# dds_ad9958.net
KiCad netlist of a schematic drawn in EAGLE
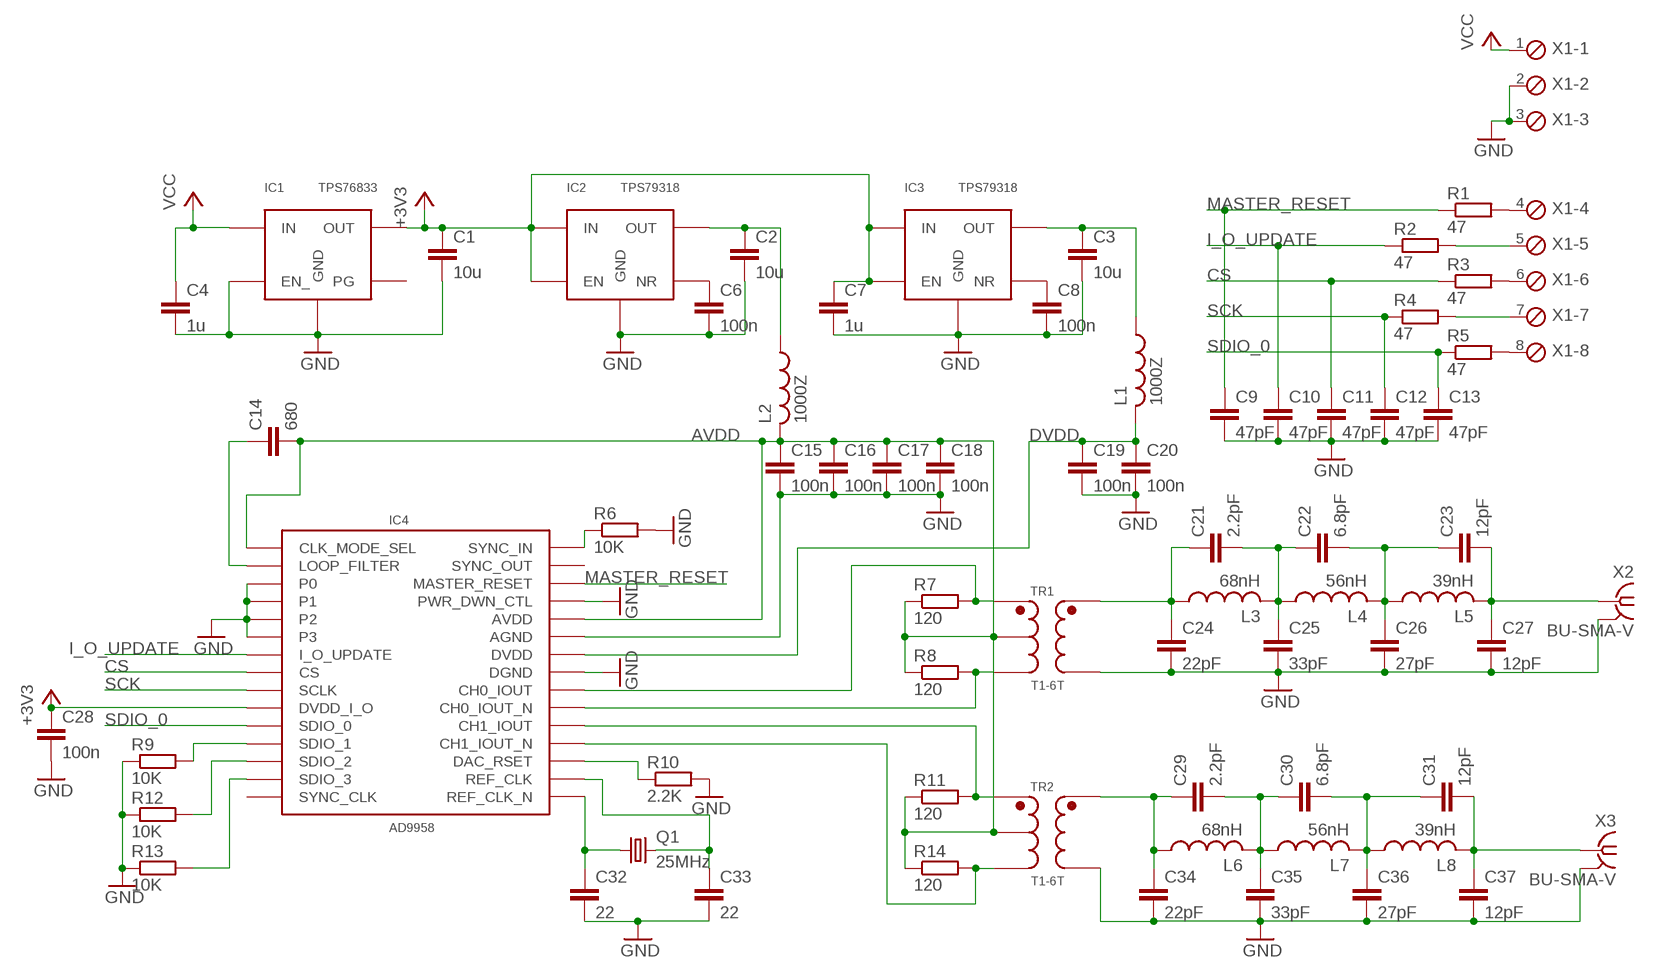
[diagram p0: schematic, sheet 1]

(export (version "E")
  (design (tool "Eeschema 10.0.6"))
  (components
    (comp (ref "C1")
      (value "10u")
      (footprint "eagle-import:C0805")
      (libsource (lib "eagle-import") (part "C-EUC0805"))
    )
    (comp (ref "C2")
      (value "10u")
      (footprint "eagle-import:C0805")
      (libsource (lib "eagle-import") (part "C-EUC0805"))
    )
    (comp (ref "C3")
      (value "10u")
      (footprint "eagle-import:C0805")
      (libsource (lib "eagle-import") (part "C-EUC0805"))
    )
    (comp (ref "C4")
      (value "1u")
      (footprint "eagle-import:C0603")
      (libsource (lib "eagle-import") (part "C-EUC0603"))
    )
    (comp (ref "C6")
      (value "100n")
      (footprint "eagle-import:C0603")
      (libsource (lib "eagle-import") (part "C-EUC0603"))
    )
    (comp (ref "C7")
      (value "1u")
      (footprint "eagle-import:C0603")
      (libsource (lib "eagle-import") (part "C-EUC0603"))
    )
    (comp (ref "C8")
      (value "100n")
      (footprint "eagle-import:C0603")
      (libsource (lib "eagle-import") (part "C-EUC0603"))
    )
    (comp (ref "C9")
      (value "47pF")
      (footprint "eagle-import:C0805")
      (libsource (lib "eagle-import") (part "C-EUC0805"))
    )
    (comp (ref "C10")
      (value "47pF")
      (footprint "eagle-import:C0805")
      (libsource (lib "eagle-import") (part "C-EUC0805"))
    )
    (comp (ref "C11")
      (value "47pF")
      (footprint "eagle-import:C0805")
      (libsource (lib "eagle-import") (part "C-EUC0805"))
    )
    (comp (ref "C12")
      (value "47pF")
      (footprint "eagle-import:C0805")
      (libsource (lib "eagle-import") (part "C-EUC0805"))
    )
    (comp (ref "C13")
      (value "47pF")
      (footprint "eagle-import:C0805")
      (libsource (lib "eagle-import") (part "C-EUC0805"))
    )
    (comp (ref "C14")
      (value "680")
      (footprint "eagle-import:C0805")
      (libsource (lib "eagle-import") (part "C-EUC0805"))
    )
    (comp (ref "C15")
      (value "100n")
      (footprint "eagle-import:C0603")
      (libsource (lib "eagle-import") (part "C-EUC0603"))
    )
    (comp (ref "C16")
      (value "100n")
      (footprint "eagle-import:C0603")
      (libsource (lib "eagle-import") (part "C-EUC0603"))
    )
    (comp (ref "C17")
      (value "100n")
      (footprint "eagle-import:C0603")
      (libsource (lib "eagle-import") (part "C-EUC0603"))
    )
    (comp (ref "C18")
      (value "100n")
      (footprint "eagle-import:C0603")
      (libsource (lib "eagle-import") (part "C-EUC0603"))
    )
    (comp (ref "C19")
      (value "100n")
      (footprint "eagle-import:C0603")
      (libsource (lib "eagle-import") (part "C-EUC0603"))
    )
    (comp (ref "C20")
      (value "100n")
      (footprint "eagle-import:C0603")
      (libsource (lib "eagle-import") (part "C-EUC0603"))
    )
    (comp (ref "C21")
      (value "2.2pF")
      (footprint "eagle-import:C0805")
      (libsource (lib "eagle-import") (part "C-EUC0805"))
    )
    (comp (ref "C22")
      (value "6.8pF")
      (footprint "eagle-import:C0805")
      (libsource (lib "eagle-import") (part "C-EUC0805"))
    )
    (comp (ref "C23")
      (value "12pF")
      (footprint "eagle-import:C0805")
      (libsource (lib "eagle-import") (part "C-EUC0805"))
    )
    (comp (ref "C24")
      (value "22pF")
      (footprint "eagle-import:C0805")
      (libsource (lib "eagle-import") (part "C-EUC0805"))
    )
    (comp (ref "C25")
      (value "33pF")
      (footprint "eagle-import:C0805")
      (libsource (lib "eagle-import") (part "C-EUC0805"))
    )
    (comp (ref "C26")
      (value "27pF")
      (footprint "eagle-import:C0805")
      (libsource (lib "eagle-import") (part "C-EUC0805"))
    )
    (comp (ref "C27")
      (value "12pF")
      (footprint "eagle-import:C0805")
      (libsource (lib "eagle-import") (part "C-EUC0805"))
    )
    (comp (ref "C28")
      (value "100n")
      (footprint "eagle-import:C0603")
      (libsource (lib "eagle-import") (part "C-EUC0603"))
    )
    (comp (ref "C29")
      (value "2.2pF")
      (footprint "eagle-import:C0805")
      (libsource (lib "eagle-import") (part "C-EUC0805"))
    )
    (comp (ref "C30")
      (value "6.8pF")
      (footprint "eagle-import:C0805")
      (libsource (lib "eagle-import") (part "C-EUC0805"))
    )
    (comp (ref "C31")
      (value "12pF")
      (footprint "eagle-import:C0805")
      (libsource (lib "eagle-import") (part "C-EUC0805"))
    )
    (comp (ref "C32")
      (value "22")
      (footprint "eagle-import:C0603")
      (libsource (lib "eagle-import") (part "C-EUC0603"))
    )
    (comp (ref "C33")
      (value "22")
      (footprint "eagle-import:C0603")
      (libsource (lib "eagle-import") (part "C-EUC0603"))
    )
    (comp (ref "C34")
      (value "22pF")
      (footprint "eagle-import:C0805")
      (libsource (lib "eagle-import") (part "C-EUC0805"))
    )
    (comp (ref "C35")
      (value "33pF")
      (footprint "eagle-import:C0805")
      (libsource (lib "eagle-import") (part "C-EUC0805"))
    )
    (comp (ref "C36")
      (value "27pF")
      (footprint "eagle-import:C0805")
      (libsource (lib "eagle-import") (part "C-EUC0805"))
    )
    (comp (ref "C37")
      (value "12pF")
      (footprint "eagle-import:C0805")
      (libsource (lib "eagle-import") (part "C-EUC0805"))
    )
    (comp (ref "IC1")
      (value "TPS76833")
      (footprint "eagle-import:SO8")
      (libsource (lib "eagle-import") (part "TPS768XX"))
    )
    (comp (ref "IC2")
      (value "TPS79318")
      (footprint "eagle-import:SOT23-5")
      (libsource (lib "eagle-import") (part "TPS793XX_FIXED"))
    )
    (comp (ref "IC3")
      (value "TPS79318")
      (footprint "eagle-import:SOT23-5")
      (libsource (lib "eagle-import") (part "TPS793XX_FIXED"))
    )
    (comp (ref "IC4")
      (value "AD9958")
      (footprint "eagle-import:CP-56-1")
      (libsource (lib "eagle-import") (part "AD9958"))
    )
    (comp (ref "L1")
      (value "1000Z")
      (footprint "eagle-import:C0805")
      (libsource (lib "eagle-import") (part "L-USL0805"))
    )
    (comp (ref "L2")
      (value "1000Z")
      (footprint "eagle-import:C0805")
      (libsource (lib "eagle-import") (part "L-USL0805"))
    )
    (comp (ref "L3")
      (value "68nH")
      (footprint "eagle-import:C0805")
      (libsource (lib "eagle-import") (part "L-USL0805"))
    )
    (comp (ref "L4")
      (value "56nH")
      (footprint "eagle-import:C0805")
      (libsource (lib "eagle-import") (part "L-USL0805"))
    )
    (comp (ref "L5")
      (value "39nH")
      (footprint "eagle-import:C0805")
      (libsource (lib "eagle-import") (part "L-USL0805"))
    )
    (comp (ref "L6")
      (value "68nH")
      (footprint "eagle-import:C0805")
      (libsource (lib "eagle-import") (part "L-USL0805"))
    )
    (comp (ref "L7")
      (value "56nH")
      (footprint "eagle-import:C0805")
      (libsource (lib "eagle-import") (part "L-USL0805"))
    )
    (comp (ref "L8")
      (value "39nH")
      (footprint "eagle-import:C0805")
      (libsource (lib "eagle-import") (part "L-USL0805"))
    )
    (comp (ref "Q1")
      (value "25MHz")
      (footprint "eagle-import:HC49_S")
      (libsource (lib "eagle-import") (part "CRYSTALHC49S"))
    )
    (comp (ref "R1")
      (value "47")
      (footprint "eagle-import:R0603")
      (libsource (lib "eagle-import") (part "R-EU_R0603"))
    )
    (comp (ref "R2")
      (value "47")
      (footprint "eagle-import:R0603")
      (libsource (lib "eagle-import") (part "R-EU_R0603"))
    )
    (comp (ref "R3")
      (value "47")
      (footprint "eagle-import:R0603")
      (libsource (lib "eagle-import") (part "R-EU_R0603"))
    )
    (comp (ref "R4")
      (value "47")
      (footprint "eagle-import:R0603")
      (libsource (lib "eagle-import") (part "R-EU_R0603"))
    )
    (comp (ref "R5")
      (value "47")
      (footprint "eagle-import:R0603")
      (libsource (lib "eagle-import") (part "R-EU_R0603"))
    )
    (comp (ref "R6")
      (value "10K")
      (footprint "eagle-import:R0603")
      (libsource (lib "eagle-import") (part "R-EU_R0603"))
    )
    (comp (ref "R7")
      (value "120")
      (footprint "eagle-import:R0603")
      (libsource (lib "eagle-import") (part "R-EU_R0603"))
    )
    (comp (ref "R8")
      (value "120")
      (footprint "eagle-import:R0603")
      (libsource (lib "eagle-import") (part "R-EU_R0603"))
    )
    (comp (ref "R9")
      (value "10K")
      (footprint "eagle-import:R0603")
      (libsource (lib "eagle-import") (part "R-EU_R0603"))
    )
    (comp (ref "R10")
      (value "2.2K")
      (footprint "eagle-import:R0603")
      (libsource (lib "eagle-import") (part "R-EU_R0603"))
    )
    (comp (ref "R11")
      (value "120")
      (footprint "eagle-import:R0603")
      (libsource (lib "eagle-import") (part "R-EU_R0603"))
    )
    (comp (ref "R12")
      (value "10K")
      (footprint "eagle-import:R0603")
      (libsource (lib "eagle-import") (part "R-EU_R0603"))
    )
    (comp (ref "R13")
      (value "10K")
      (footprint "eagle-import:R0603")
      (libsource (lib "eagle-import") (part "R-EU_R0603"))
    )
    (comp (ref "R14")
      (value "120")
      (footprint "eagle-import:R0603")
      (libsource (lib "eagle-import") (part "R-EU_R0603"))
    )
    (comp (ref "TR1")
      (value "T1-6T")
      (footprint "eagle-import:KK81")
      (libsource (lib "eagle-import") (part "T1-6T"))
    )
    (comp (ref "TR2")
      (value "T1-6T")
      (footprint "eagle-import:KK81")
      (libsource (lib "eagle-import") (part "T1-6T"))
    )
    (comp (ref "X1")
      (value "MPT8")
      (footprint "eagle-import:8POL254")
      (libsource (lib "eagle-import") (part "MPT8"))
    )
    (comp (ref "X2")
      (value "BU-SMA-V")
      (footprint "eagle-import:BU-SMA-V")
      (libsource (lib "eagle-import") (part "BU-SMA-V"))
    )
    (comp (ref "X3")
      (value "BU-SMA-V")
      (footprint "eagle-import:BU-SMA-V")
      (libsource (lib "eagle-import") (part "BU-SMA-V"))
    )
  )
  (nets
    (net (code "1") (name "+3V3") (class "Default")
      (node (ref "C1") (pin "1") (pinfunction "1_1") (pintype "passive"))
      (node (ref "C28") (pin "1") (pinfunction "1_1") (pintype "passive"))
      (node (ref "C7") (pin "1") (pinfunction "1_1") (pintype "passive"))
      (node (ref "IC1") (pin "5") (pinfunction "OUT_5") (pintype "bidirectional"))
      (node (ref "IC1") (pin "6") (pinfunction "OUT_6") (pintype "bidirectional"))
      (node (ref "IC2") (pin "1") (pinfunction "IN_1") (pintype "bidirectional"))
      (node (ref "IC2") (pin "3") (pinfunction "EN_3") (pintype "bidirectional"))
      (node (ref "IC3") (pin "1") (pinfunction "IN_1") (pintype "bidirectional"))
      (node (ref "IC3") (pin "3") (pinfunction "EN_3") (pintype "bidirectional"))
      (node (ref "IC4") (pin "P$49") (pinfunction "DVDD_I_O_P$49") (pintype "bidirectional"))
    )
    (net (code "2") (name "/AVDD") (class "Default")
      (node (ref "C14") (pin "2") (pinfunction "2_2") (pintype "passive"))
      (node (ref "C15") (pin "1") (pinfunction "1_1") (pintype "passive"))
      (node (ref "C16") (pin "1") (pinfunction "1_1") (pintype "passive"))
      (node (ref "C17") (pin "1") (pinfunction "1_1") (pintype "passive"))
      (node (ref "C18") (pin "1") (pinfunction "1_1") (pintype "passive"))
      (node (ref "IC4") (pin "P$11") (pinfunction "AVDD_P$11") (pintype "bidirectional"))
      (node (ref "IC4") (pin "P$15") (pinfunction "AVDD_P$15") (pintype "bidirectional"))
      (node (ref "IC4") (pin "P$19") (pinfunction "AVDD_P$19") (pintype "bidirectional"))
      (node (ref "IC4") (pin "P$21") (pinfunction "AVDD_P$21") (pintype "bidirectional"))
      (node (ref "IC4") (pin "P$24") (pinfunction "CLK_MODE_SEL_P$24") (pintype "bidirectional"))
      (node (ref "IC4") (pin "P$26") (pinfunction "AVDD_P$26") (pintype "bidirectional"))
      (node (ref "IC4") (pin "P$29") (pinfunction "AVDD_P$29") (pintype "bidirectional"))
      (node (ref "IC4") (pin "P$30") (pinfunction "AVDD_P$30") (pintype "bidirectional"))
      (node (ref "IC4") (pin "P$31") (pinfunction "AVDD_P$31") (pintype "bidirectional"))
      (node (ref "IC4") (pin "P$33") (pinfunction "AVDD_P$33") (pintype "bidirectional"))
      (node (ref "IC4") (pin "P$35") (pinfunction "AVDD_P$35") (pintype "bidirectional"))
      (node (ref "IC4") (pin "P$36") (pinfunction "AVDD_P$36") (pintype "bidirectional"))
      (node (ref "IC4") (pin "P$37") (pinfunction "AVDD_P$37") (pintype "bidirectional"))
      (node (ref "IC4") (pin "P$39") (pinfunction "AVDD_P$39") (pintype "bidirectional"))
      (node (ref "IC4") (pin "P$5") (pinfunction "AVDD_P$5") (pintype "bidirectional"))
      (node (ref "IC4") (pin "P$7") (pinfunction "AVDD_P$7") (pintype "bidirectional"))
      (node (ref "L2") (pin "2") (pinfunction "2_2") (pintype "passive"))
      (node (ref "R11") (pin "1") (pinfunction "1_1") (pintype "passive"))
      (node (ref "R14") (pin "1") (pinfunction "1_1") (pintype "passive"))
      (node (ref "R7") (pin "1") (pinfunction "1_1") (pintype "passive"))
      (node (ref "R8") (pin "1") (pinfunction "1_1") (pintype "passive"))
      (node (ref "TR1") (pin "P$2") (pinfunction "SEC_CT_P$2") (pintype "bidirectional"))
      (node (ref "TR2") (pin "P$2") (pinfunction "SEC_CT_P$2") (pintype "bidirectional"))
    )
    (net (code "3") (name "/CS") (class "Default")
      (node (ref "C11") (pin "1") (pinfunction "1_1") (pintype "passive"))
      (node (ref "IC4") (pin "P$47") (pinfunction "CS_P$47") (pintype "bidirectional"))
      (node (ref "R3") (pin "1") (pinfunction "1_1") (pintype "passive"))
    )
    (net (code "4") (name "/DVDD") (class "Default")
      (node (ref "C19") (pin "1") (pinfunction "1_1") (pintype "passive"))
      (node (ref "C20") (pin "1") (pinfunction "1_1") (pintype "passive"))
      (node (ref "IC4") (pin "P$45") (pinfunction "DVDD_P$45") (pintype "bidirectional"))
      (node (ref "IC4") (pin "P$55") (pinfunction "DVDD_P$55") (pintype "bidirectional"))
      (node (ref "L1") (pin "2") (pinfunction "2_2") (pintype "passive"))
    )
    (net (code "5") (name "/I_O_UPDATE") (class "Default")
      (node (ref "C10") (pin "1") (pinfunction "1_1") (pintype "passive"))
      (node (ref "IC4") (pin "P$46") (pinfunction "I_O_UPDATE_P$46") (pintype "bidirectional"))
      (node (ref "R2") (pin "1") (pinfunction "1_1") (pintype "passive"))
    )
    (net (code "6") (name "/MASTER_RESET") (class "Default")
      (node (ref "C9") (pin "1") (pinfunction "1_1") (pintype "passive"))
      (node (ref "IC4") (pin "P$3") (pinfunction "MASTER_RESET_P$3") (pintype "bidirectional"))
      (node (ref "R1") (pin "1") (pinfunction "1_1") (pintype "passive"))
    )
    (net (code "7") (name "/SCK") (class "Default")
      (node (ref "C12") (pin "1") (pinfunction "1_1") (pintype "passive"))
      (node (ref "IC4") (pin "P$48") (pinfunction "SCLK_P$48") (pintype "bidirectional"))
      (node (ref "R4") (pin "1") (pinfunction "1_1") (pintype "passive"))
    )
    (net (code "8") (name "/SDIO_0") (class "Default")
      (node (ref "C13") (pin "1") (pinfunction "1_1") (pintype "passive"))
      (node (ref "IC4") (pin "P$50") (pinfunction "SDIO_0_P$50") (pintype "bidirectional"))
      (node (ref "R5") (pin "1") (pinfunction "1_1") (pintype "passive"))
    )
    (net (code "9") (name "GND") (class "Default")
      (node (ref "C1") (pin "2") (pinfunction "2_2") (pintype "passive"))
      (node (ref "C10") (pin "2") (pinfunction "2_2") (pintype "passive"))
      (node (ref "C11") (pin "2") (pinfunction "2_2") (pintype "passive"))
      (node (ref "C12") (pin "2") (pinfunction "2_2") (pintype "passive"))
      (node (ref "C13") (pin "2") (pinfunction "2_2") (pintype "passive"))
      (node (ref "C15") (pin "2") (pinfunction "2_2") (pintype "passive"))
      (node (ref "C16") (pin "2") (pinfunction "2_2") (pintype "passive"))
      (node (ref "C17") (pin "2") (pinfunction "2_2") (pintype "passive"))
      (node (ref "C18") (pin "2") (pinfunction "2_2") (pintype "passive"))
      (node (ref "C19") (pin "2") (pinfunction "2_2") (pintype "passive"))
      (node (ref "C2") (pin "2") (pinfunction "2_2") (pintype "passive"))
      (node (ref "C20") (pin "2") (pinfunction "2_2") (pintype "passive"))
      (node (ref "C24") (pin "2") (pinfunction "2_2") (pintype "passive"))
      (node (ref "C25") (pin "2") (pinfunction "2_2") (pintype "passive"))
      (node (ref "C26") (pin "2") (pinfunction "2_2") (pintype "passive"))
      (node (ref "C27") (pin "2") (pinfunction "2_2") (pintype "passive"))
      (node (ref "C28") (pin "2") (pinfunction "2_2") (pintype "passive"))
      (node (ref "C3") (pin "2") (pinfunction "2_2") (pintype "passive"))
      (node (ref "C32") (pin "2") (pinfunction "2_2") (pintype "passive"))
      (node (ref "C33") (pin "2") (pinfunction "2_2") (pintype "passive"))
      (node (ref "C34") (pin "2") (pinfunction "2_2") (pintype "passive"))
      (node (ref "C35") (pin "2") (pinfunction "2_2") (pintype "passive"))
      (node (ref "C36") (pin "2") (pinfunction "2_2") (pintype "passive"))
      (node (ref "C37") (pin "2") (pinfunction "2_2") (pintype "passive"))
      (node (ref "C4") (pin "2") (pinfunction "2_2") (pintype "passive"))
      (node (ref "C6") (pin "2") (pinfunction "2_2") (pintype "passive"))
      (node (ref "C7") (pin "2") (pinfunction "2_2") (pintype "passive"))
      (node (ref "C8") (pin "2") (pinfunction "2_2") (pintype "passive"))
      (node (ref "C9") (pin "2") (pinfunction "2_2") (pintype "passive"))
      (node (ref "IC1") (pin "1") (pinfunction "GND_1") (pintype "bidirectional"))
      (node (ref "IC1") (pin "2") (pinfunction "EN__2") (pintype "bidirectional"))
      (node (ref "IC2") (pin "2") (pinfunction "GND_2") (pintype "bidirectional"))
      (node (ref "IC3") (pin "2") (pinfunction "GND_2") (pintype "bidirectional"))
      (node (ref "IC4") (pin "P$10") (pinfunction "AGND_P$10") (pintype "bidirectional"))
      (node (ref "IC4") (pin "P$12") (pinfunction "AGND_P$12") (pintype "bidirectional"))
      (node (ref "IC4") (pin "P$16") (pinfunction "AGND_P$16") (pintype "bidirectional"))
      (node (ref "IC4") (pin "P$18") (pinfunction "AGND_P$18") (pintype "bidirectional"))
      (node (ref "IC4") (pin "P$20") (pinfunction "AGND_P$20") (pintype "bidirectional"))
      (node (ref "IC4") (pin "P$25") (pinfunction "AGND_P$25") (pintype "bidirectional"))
      (node (ref "IC4") (pin "P$4") (pinfunction "PWR_DWN_CTL_P$4") (pintype "bidirectional"))
      (node (ref "IC4") (pin "P$40") (pinfunction "P0_P$40") (pintype "bidirectional"))
      (node (ref "IC4") (pin "P$41") (pinfunction "P1_P$41") (pintype "bidirectional"))
      (node (ref "IC4") (pin "P$42") (pinfunction "P2_P$42") (pintype "bidirectional"))
      (node (ref "IC4") (pin "P$43") (pinfunction "P3_P$43") (pintype "bidirectional"))
      (node (ref "IC4") (pin "P$44") (pinfunction "DGND_P$44") (pintype "bidirectional"))
      (node (ref "IC4") (pin "P$56") (pinfunction "DGND_P$56") (pintype "bidirectional"))
      (node (ref "IC4") (pin "P$6") (pinfunction "AGND_P$6") (pintype "bidirectional"))
      (node (ref "IC4") (pin "PAD") (pinfunction "AGND_PAD") (pintype "bidirectional"))
      (node (ref "R10") (pin "2") (pinfunction "2_2") (pintype "passive"))
      (node (ref "R12") (pin "1") (pinfunction "1_1") (pintype "passive"))
      (node (ref "R13") (pin "1") (pinfunction "1_1") (pintype "passive"))
      (node (ref "R6") (pin "2") (pinfunction "2_2") (pintype "passive"))
      (node (ref "R9") (pin "1") (pinfunction "1_1") (pintype "passive"))
      (node (ref "TR1") (pin "P$6") (pinfunction "PRI_P$6") (pintype "bidirectional"))
      (node (ref "TR2") (pin "P$6") (pinfunction "PRI_P$6") (pintype "bidirectional"))
      (node (ref "X1") (pin "2") (pinfunction "1_2") (pintype "passive"))
      (node (ref "X1") (pin "3") (pinfunction "1_3") (pintype "passive"))
      (node (ref "X2") (pin "2") (pinfunction "2_2") (pintype "passive"))
      (node (ref "X2") (pin "3") (pinfunction "2_3") (pintype "passive"))
      (node (ref "X2") (pin "4") (pinfunction "2_4") (pintype "passive"))
      (node (ref "X2") (pin "5") (pinfunction "2_5") (pintype "passive"))
      (node (ref "X3") (pin "2") (pinfunction "2_2") (pintype "passive"))
      (node (ref "X3") (pin "3") (pinfunction "2_3") (pintype "passive"))
      (node (ref "X3") (pin "4") (pinfunction "2_4") (pintype "passive"))
      (node (ref "X3") (pin "5") (pinfunction "2_5") (pintype "passive"))
    )
    (net (code "10") (name "Net-(C21-Pad2)") (class "Default")
      (node (ref "C21") (pin "2") (pinfunction "2_2") (pintype "passive"))
      (node (ref "C22") (pin "1") (pinfunction "1_1") (pintype "passive"))
      (node (ref "C25") (pin "1") (pinfunction "1_1") (pintype "passive"))
      (node (ref "L3") (pin "2") (pinfunction "2_2") (pintype "passive"))
      (node (ref "L4") (pin "1") (pinfunction "1_1") (pintype "passive"))
    )
    (net (code "11") (name "Net-(C22-Pad2)") (class "Default")
      (node (ref "C22") (pin "2") (pinfunction "2_2") (pintype "passive"))
      (node (ref "C23") (pin "1") (pinfunction "1_1") (pintype "passive"))
      (node (ref "C26") (pin "1") (pinfunction "1_1") (pintype "passive"))
      (node (ref "L4") (pin "2") (pinfunction "2_2") (pintype "passive"))
      (node (ref "L5") (pin "1") (pinfunction "1_1") (pintype "passive"))
    )
    (net (code "12") (name "Net-(C23-Pad2)") (class "Default")
      (node (ref "C23") (pin "2") (pinfunction "2_2") (pintype "passive"))
      (node (ref "C27") (pin "1") (pinfunction "1_1") (pintype "passive"))
      (node (ref "L5") (pin "2") (pinfunction "2_2") (pintype "passive"))
      (node (ref "X2") (pin "1") (pinfunction "1_1") (pintype "passive"))
    )
    (net (code "13") (name "Net-(C29-Pad2)") (class "Default")
      (node (ref "C29") (pin "2") (pinfunction "2_2") (pintype "passive"))
      (node (ref "C30") (pin "1") (pinfunction "1_1") (pintype "passive"))
      (node (ref "C35") (pin "1") (pinfunction "1_1") (pintype "passive"))
      (node (ref "L6") (pin "2") (pinfunction "2_2") (pintype "passive"))
      (node (ref "L7") (pin "1") (pinfunction "1_1") (pintype "passive"))
    )
    (net (code "14") (name "Net-(C30-Pad2)") (class "Default")
      (node (ref "C30") (pin "2") (pinfunction "2_2") (pintype "passive"))
      (node (ref "C31") (pin "1") (pinfunction "1_1") (pintype "passive"))
      (node (ref "C36") (pin "1") (pinfunction "1_1") (pintype "passive"))
      (node (ref "L7") (pin "2") (pinfunction "2_2") (pintype "passive"))
      (node (ref "L8") (pin "1") (pinfunction "1_1") (pintype "passive"))
    )
    (net (code "15") (name "Net-(C31-Pad2)") (class "Default")
      (node (ref "C31") (pin "2") (pinfunction "2_2") (pintype "passive"))
      (node (ref "C37") (pin "1") (pinfunction "1_1") (pintype "passive"))
      (node (ref "L8") (pin "2") (pinfunction "2_2") (pintype "passive"))
      (node (ref "X3") (pin "1") (pinfunction "1_1") (pintype "passive"))
    )
    (net (code "16") (name "Net-(IC2-NR)") (class "Default")
      (node (ref "C6") (pin "1") (pinfunction "1_1") (pintype "passive"))
      (node (ref "IC2") (pin "4") (pinfunction "NR_4") (pintype "bidirectional"))
    )
    (net (code "17") (name "Net-(IC2-OUT)") (class "Default")
      (node (ref "C2") (pin "1") (pinfunction "1_1") (pintype "passive"))
      (node (ref "IC2") (pin "5") (pinfunction "OUT_5") (pintype "bidirectional"))
      (node (ref "L2") (pin "1") (pinfunction "1_1") (pintype "passive"))
    )
    (net (code "18") (name "Net-(IC3-NR)") (class "Default")
      (node (ref "C8") (pin "1") (pinfunction "1_1") (pintype "passive"))
      (node (ref "IC3") (pin "4") (pinfunction "NR_4") (pintype "bidirectional"))
    )
    (net (code "19") (name "Net-(IC3-OUT)") (class "Default")
      (node (ref "C3") (pin "1") (pinfunction "1_1") (pintype "passive"))
      (node (ref "IC3") (pin "5") (pinfunction "OUT_5") (pintype "bidirectional"))
      (node (ref "L1") (pin "1") (pinfunction "1_1") (pintype "passive"))
    )
    (net (code "20") (name "Net-(IC4-CH0_IOUT)") (class "Default")
      (node (ref "IC4") (pin "P$8") (pinfunction "CH0_IOUT_P$8") (pintype "bidirectional"))
      (node (ref "R7") (pin "2") (pinfunction "2_2") (pintype "passive"))
      (node (ref "TR1") (pin "P$3") (pinfunction "SEC_DOT_P$3") (pintype "bidirectional"))
    )
    (net (code "21") (name "Net-(IC4-CH0_IOUT_N)") (class "Default")
      (node (ref "IC4") (pin "P$9") (pinfunction "CH0_IOUT_N_P$9") (pintype "bidirectional"))
      (node (ref "R8") (pin "2") (pinfunction "2_2") (pintype "passive"))
      (node (ref "TR1") (pin "P$1") (pinfunction "SEC_P$1") (pintype "bidirectional"))
    )
    (net (code "22") (name "Net-(IC4-CH1_IOUT)") (class "Default")
      (node (ref "IC4") (pin "P$13") (pinfunction "CH1_IOUT_P$13") (pintype "bidirectional"))
      (node (ref "R11") (pin "2") (pinfunction "2_2") (pintype "passive"))
      (node (ref "TR2") (pin "P$3") (pinfunction "SEC_DOT_P$3") (pintype "bidirectional"))
    )
    (net (code "23") (name "Net-(IC4-CH1_IOUT_N)") (class "Default")
      (node (ref "IC4") (pin "P$14") (pinfunction "CH1_IOUT_N_P$14") (pintype "bidirectional"))
      (node (ref "R14") (pin "2") (pinfunction "2_2") (pintype "passive"))
      (node (ref "TR2") (pin "P$1") (pinfunction "SEC_P$1") (pintype "bidirectional"))
    )
    (net (code "24") (name "Net-(IC4-DAC_RSET)") (class "Default")
      (node (ref "IC4") (pin "P$17") (pinfunction "DAC_RSET_P$17") (pintype "bidirectional"))
      (node (ref "R10") (pin "1") (pinfunction "1_1") (pintype "passive"))
    )
    (net (code "25") (name "Net-(IC4-LOOP_FILTER)") (class "Default")
      (node (ref "C14") (pin "1") (pinfunction "1_1") (pintype "passive"))
      (node (ref "IC4") (pin "P$27") (pinfunction "LOOP_FILTER_P$27") (pintype "bidirectional"))
    )
    (net (code "26") (name "Net-(IC4-REF_CLK)") (class "Default")
      (node (ref "C33") (pin "1") (pinfunction "1_1") (pintype "passive"))
      (node (ref "IC4") (pin "P$23") (pinfunction "REF_CLK_P$23") (pintype "bidirectional"))
      (node (ref "Q1") (pin "2") (pinfunction "2_2") (pintype "passive"))
    )
    (net (code "27") (name "Net-(IC4-REF_CLK_N)") (class "Default")
      (node (ref "C32") (pin "1") (pinfunction "1_1") (pintype "passive"))
      (node (ref "IC4") (pin "P$22") (pinfunction "REF_CLK_N_P$22") (pintype "bidirectional"))
      (node (ref "Q1") (pin "1") (pinfunction "1_1") (pintype "passive"))
    )
    (net (code "28") (name "Net-(IC4-SDIO_1)") (class "Default")
      (node (ref "IC4") (pin "P$51") (pinfunction "SDIO_1_P$51") (pintype "bidirectional"))
      (node (ref "R9") (pin "2") (pinfunction "2_2") (pintype "passive"))
    )
    (net (code "29") (name "Net-(IC4-SDIO_2)") (class "Default")
      (node (ref "IC4") (pin "P$52") (pinfunction "SDIO_2_P$52") (pintype "bidirectional"))
      (node (ref "R12") (pin "2") (pinfunction "2_2") (pintype "passive"))
    )
    (net (code "30") (name "Net-(IC4-SDIO_3)") (class "Default")
      (node (ref "IC4") (pin "P$53") (pinfunction "SDIO_3_P$53") (pintype "bidirectional"))
      (node (ref "R13") (pin "2") (pinfunction "2_2") (pintype "passive"))
    )
    (net (code "31") (name "Net-(IC4-SYNC_IN)") (class "Default")
      (node (ref "IC4") (pin "P$1") (pinfunction "SYNC_IN_P$1") (pintype "bidirectional"))
      (node (ref "R6") (pin "1") (pinfunction "1_1") (pintype "passive"))
    )
    (net (code "32") (name "Net-(TR1-PRI_DOT)") (class "Default")
      (node (ref "C21") (pin "1") (pinfunction "1_1") (pintype "passive"))
      (node (ref "C24") (pin "1") (pinfunction "1_1") (pintype "passive"))
      (node (ref "L3") (pin "1") (pinfunction "1_1") (pintype "passive"))
      (node (ref "TR1") (pin "P$4") (pinfunction "PRI_DOT_P$4") (pintype "bidirectional"))
    )
    (net (code "33") (name "Net-(TR2-PRI_DOT)") (class "Default")
      (node (ref "C29") (pin "1") (pinfunction "1_1") (pintype "passive"))
      (node (ref "C34") (pin "1") (pinfunction "1_1") (pintype "passive"))
      (node (ref "L6") (pin "1") (pinfunction "1_1") (pintype "passive"))
      (node (ref "TR2") (pin "P$4") (pinfunction "PRI_DOT_P$4") (pintype "bidirectional"))
    )
    (net (code "34") (name "Net-(X1D-1)") (class "Default")
      (node (ref "R1") (pin "2") (pinfunction "2_2") (pintype "passive"))
      (node (ref "X1") (pin "4") (pinfunction "1_4") (pintype "passive"))
    )
    (net (code "35") (name "Net-(X1E-1)") (class "Default")
      (node (ref "R2") (pin "2") (pinfunction "2_2") (pintype "passive"))
      (node (ref "X1") (pin "5") (pinfunction "1_5") (pintype "passive"))
    )
    (net (code "36") (name "Net-(X1F-1)") (class "Default")
      (node (ref "R3") (pin "2") (pinfunction "2_2") (pintype "passive"))
      (node (ref "X1") (pin "6") (pinfunction "1_6") (pintype "passive"))
    )
    (net (code "37") (name "Net-(X1G-1)") (class "Default")
      (node (ref "R4") (pin "2") (pinfunction "2_2") (pintype "passive"))
      (node (ref "X1") (pin "7") (pinfunction "1_7") (pintype "passive"))
    )
    (net (code "38") (name "Net-(X1H-1)") (class "Default")
      (node (ref "R5") (pin "2") (pinfunction "2_2") (pintype "passive"))
      (node (ref "X1") (pin "8") (pinfunction "1_8") (pintype "passive"))
    )
    (net (code "39") (name "VCC") (class "Default")
      (node (ref "C4") (pin "1") (pinfunction "1_1") (pintype "passive"))
      (node (ref "IC1") (pin "3") (pinfunction "IN_3") (pintype "bidirectional"))
      (node (ref "IC1") (pin "4") (pinfunction "IN_4") (pintype "bidirectional"))
      (node (ref "X1") (pin "1") (pinfunction "1_1") (pintype "passive"))
    )
    (net (code "40") (name "unconnected-(IC1-PG-Pad8)") (class "Default")
      (node (ref "IC1") (pin "8") (pinfunction "PG_8") (pintype "bidirectional"))
    )
    (net (code "41") (name "unconnected-(IC4-SYNC_CLK-PadP$54)") (class "Default")
      (node (ref "IC4") (pin "P$54") (pinfunction "SYNC_CLK_P$54") (pintype "bidirectional"))
    )
    (net (code "42") (name "unconnected-(IC4-SYNC_OUT-PadP$2)") (class "Default")
      (node (ref "IC4") (pin "P$2") (pinfunction "SYNC_OUT_P$2") (pintype "bidirectional"))
    )
  )
)
